# Arduino_Shield.net
KiCad netlist of a schematic drawn in Altium Designer
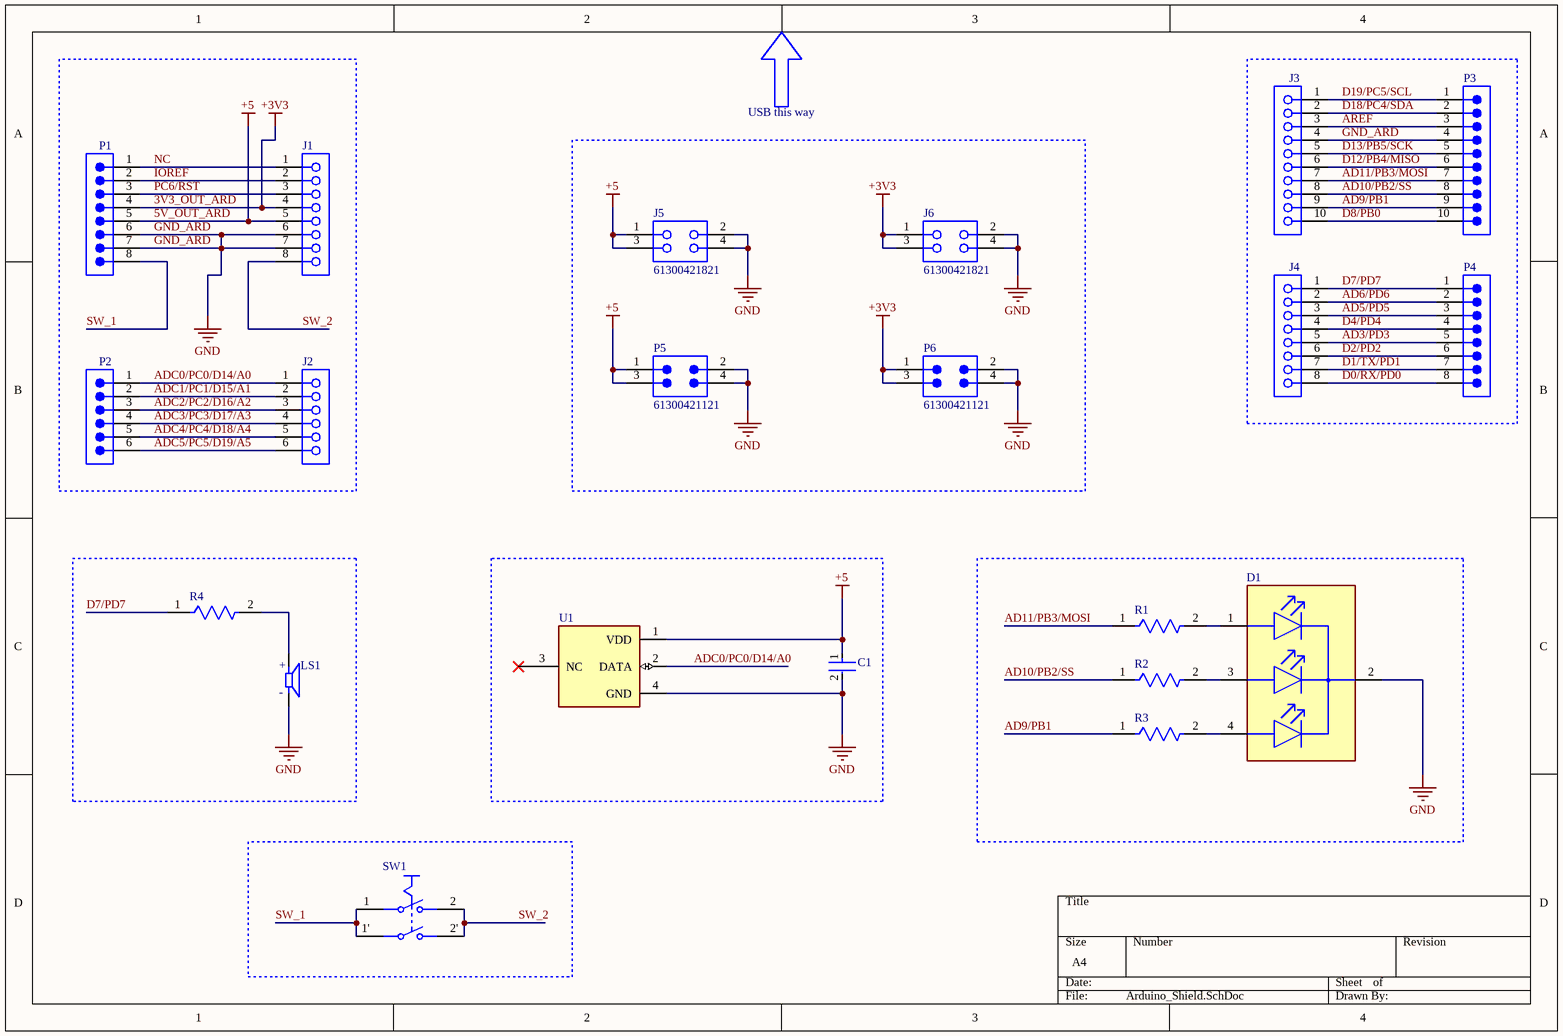
[diagram p0: Arduino_Shield.SchDoc]

(export (version "E")
  (design (tool "Eeschema 10.0.6"))
  (components
    (comp (ref "C1")
      (value "C0402C104K4RACAUTO")
      (footprint "FP-C0402-BB-MFG")
      (description "CAP CER 0.1UF 16V X7R 0402")
      (fields
        (field (name "TOLERANCE") "0.1")
        (field (name "OCTOPART") "https://octopart.com/c0402c104k4racauto-kemet-17309149")
      )
      (libsource (lib "Altium Content Vault") (part "b4654b650e69147ec39a6b967a45e02"))
    )
    (comp (ref "D1")
      (value "AAA3528LSEKJ3ZGKQBKS")
      (footprint "FP-AAA3528LSEKJ3ZGKQBKS-MFG")
      (description "LED RGB CLEAR 4SMD")
      (libsource (lib "Altium Content Vault") (part "443e5383a7a0c9f1439af3e1184479d"))
    )
    (comp (ref "J1")
      (value "61300811821")
      (footprint "61300811821")
      (description "Btb Conn, Rcpt, 8Pos, 1Row, 2.54Mm Rohs Compliant: Yes")
      (libsource (lib "Altium Content Vault") (part "Header_Female_1R_08P"))
    )
    (comp (ref "J2")
      (value "61300611821")
      (footprint "61300611821")
      (description "THT Vertical Socket Header WR-PHD, Pitch 2.54 mm, Single Row, 6 pins")
      (libsource (lib "Altium Content Vault") (part "Header_Female_1R_06P"))
    )
    (comp (ref "J3")
      (value "61301011821")
      (footprint "61301011821")
      (description "THT Vertical Socket Header WR-PHD, Pitch 2.54 mm, Single Row, 10 pins")
      (libsource (lib "Altium Content Vault") (part "Header_Female_1R_10P"))
    )
    (comp (ref "J4")
      (value "61300811821")
      (footprint "61300811821")
      (description "Btb Conn, Rcpt, 8Pos, 1Row, 2.54Mm Rohs Compliant: Yes")
      (libsource (lib "Altium Content Vault") (part "Header_Female_1R_08P"))
    )
    (comp (ref "J5")
      (value "61300421821")
      (footprint "61300421821")
      (description "THT Vertical Socket Header WR-PHD, Pitch 2.54 mm, Dual Row, 4 pins")
      (libsource (lib "Altium Content Vault") (part "Header_Female_2R_04P"))
    )
    (comp (ref "J6")
      (value "61300421821")
      (footprint "61300421821")
      (description "THT Vertical Socket Header WR-PHD, Pitch 2.54 mm, Dual Row, 4 pins")
      (libsource (lib "Altium Content Vault") (part "Header_Female_2R_04P"))
    )
    (comp (ref "LS1")
      (value "CST-951AP")
      (footprint "CUI_CST-951AP")
      (description "9 mm, 5 V, 85 dB, Through Hole, Magnetic Audio Transducer Buzzer")
      (fields (field (name "MF") "Same Sky"))
      (libsource (lib "CST-951AP") (part "CST-951AP"))
    )
    (comp (ref "P1")
      (value "61300811121")
      (footprint "61300811121")
      (description "THT Vertical Pin Header WR-PHD, Pitch 2.54 mm, Single Row, 8 pins")
      (libsource (lib "Altium Content Vault") (part "Header_Male_1R_08P"))
    )
    (comp (ref "P2")
      (value "61300611121")
      (footprint "61300611121")
      (description "THT Vertical Pin Header WR-PHD, Pitch 2.54 mm, Single Row, 6 pins")
      (libsource (lib "Altium Content Vault") (part "Header_Male_1R_06P"))
    )
    (comp (ref "P3")
      (value "61301011121")
      (footprint "61301011121")
      (description "THT Vertical Pin Header WR-PHD, Pitch 2.54 mm, Single Row, 10 pins")
      (libsource (lib "Altium Content Vault") (part "Header_Male_1R_10P"))
    )
    (comp (ref "P4")
      (value "61300811121")
      (footprint "61300811121")
      (description "THT Vertical Pin Header WR-PHD, Pitch 2.54 mm, Single Row, 8 pins")
      (libsource (lib "Altium Content Vault") (part "Header_Male_1R_08P"))
    )
    (comp (ref "P5")
      (value "61300421121")
      (footprint "61300421121")
      (description "THT Vertical Pin Header WR-PHD, Pitch 2.54 mm, Dual Row, 4 pins")
      (libsource (lib "Altium Content Vault") (part "Header_Male_2R_04P"))
    )
    (comp (ref "P6")
      (value "61300421121")
      (footprint "61300421121")
      (description "THT Vertical Pin Header WR-PHD, Pitch 2.54 mm, Dual Row, 4 pins")
      (libsource (lib "Altium Content Vault") (part "Header_Male_2R_04P"))
    )
    (comp (ref "R1")
      (value "CPF0603F1K0C1")
      (footprint "FP-CPF0603-MFG")
      (description "RES SMD 1.0KΩ 1% 1/16W 0603")
      (fields
        (field (name "OCTOPART") "https://octopart.com/cpf0603f1k0c1-te+connectivity-42013134")
        (field (name "TOLERANCE") "1%")
      )
      (libsource (lib "Altium Content Vault") (part "1029c3af85768c4190bb7ad29bc67b5"))
    )
    (comp (ref "R2")
      (value "CPF0603F1K0C1")
      (footprint "FP-CPF0603-MFG")
      (description "RES SMD 1.0KΩ 1% 1/16W 0603")
      (fields
        (field (name "OCTOPART") "https://octopart.com/cpf0603f1k0c1-te+connectivity-42013134")
        (field (name "TOLERANCE") "1%")
      )
      (libsource (lib "Altium Content Vault") (part "1029c3af85768c4190bb7ad29bc67b5"))
    )
    (comp (ref "R3")
      (value "CPF0603F1K0C1")
      (footprint "FP-CPF0603-MFG")
      (description "RES SMD 1.0KΩ 1% 1/16W 0603")
      (fields
        (field (name "OCTOPART") "https://octopart.com/cpf0603f1k0c1-te+connectivity-42013134")
        (field (name "TOLERANCE") "1%")
      )
      (libsource (lib "Altium Content Vault") (part "1029c3af85768c4190bb7ad29bc67b5"))
    )
    (comp (ref "R4")
      (value "CPF0603F1K0C1")
      (footprint "FP-CPF0603-MFG")
      (description "RES SMD 1.0KΩ 1% 1/16W 0603")
      (fields
        (field (name "OCTOPART") "https://octopart.com/cpf0603f1k0c1-te+connectivity-42013134")
        (field (name "TOLERANCE") "1%")
      )
      (libsource (lib "Altium Content Vault") (part "1029c3af85768c4190bb7ad29bc67b5"))
    )
    (comp (ref "SW1")
      (value "PVA1EEH11.2NV2")
      (footprint "FP-PVA1EEH11_2NV2-MFG")
      (description "SWITCH PUSH DPST 0.1A 32V")
      (libsource (lib "Altium Content Vault") (part "0a7b0f685d7af6e0316c3509192f32d"))
    )
    (comp (ref "U1")
      (value "ADA386")
      (footprint "XDCR_ADA386")
      (description "DHT11 basic temperature-humidity sensor + extras")
      (fields (field (name "MF") "Adafruit Industries"))
      (libsource (lib "ADA386") (part "ADA386"))
    )
  )
  (nets
    (net (code "1") (name "+3V3") (class "Default")
      (node (ref "J1") (pin "4") (pinfunction "4_4") (pintype "passive"))
      (node (ref "J6") (pin "1") (pinfunction "1_1") (pintype "passive"))
      (node (ref "J6") (pin "3") (pinfunction "3_3") (pintype "passive"))
      (node (ref "P1") (pin "4") (pinfunction "4_4") (pintype "passive"))
      (node (ref "P6") (pin "1") (pinfunction "1_1") (pintype "passive"))
      (node (ref "P6") (pin "3") (pinfunction "3_3") (pintype "passive"))
    )
    (net (code "2") (name "+5") (class "Default")
      (node (ref "C1") (pin "1") (pinfunction "1_1") (pintype "passive"))
      (node (ref "J1") (pin "5") (pinfunction "5_5") (pintype "passive"))
      (node (ref "J5") (pin "1") (pinfunction "1_1") (pintype "passive"))
      (node (ref "J5") (pin "3") (pinfunction "3_3") (pintype "passive"))
      (node (ref "P1") (pin "5") (pinfunction "5_5") (pintype "passive"))
      (node (ref "P5") (pin "1") (pinfunction "1_1") (pintype "passive"))
      (node (ref "P5") (pin "3") (pinfunction "3_3") (pintype "passive"))
      (node (ref "U1") (pin "1") (pinfunction "VDD_1") (pintype "power_in"))
    )
    (net (code "3") (name "/AD3{slash}PD3") (class "Default")
      (node (ref "J4") (pin "5") (pinfunction "5_5") (pintype "passive"))
      (node (ref "P4") (pin "5") (pinfunction "5_5") (pintype "passive"))
    )
    (net (code "4") (name "/AD5{slash}PD5") (class "Default")
      (node (ref "J4") (pin "3") (pinfunction "3_3") (pintype "passive"))
      (node (ref "P4") (pin "3") (pinfunction "3_3") (pintype "passive"))
    )
    (net (code "5") (name "/AD6{slash}PD6") (class "Default")
      (node (ref "J4") (pin "2") (pinfunction "2_2") (pintype "passive"))
      (node (ref "P4") (pin "2") (pinfunction "2_2") (pintype "passive"))
    )
    (net (code "6") (name "/AD9{slash}PB1") (class "Default")
      (node (ref "J3") (pin "9") (pinfunction "9_9") (pintype "passive"))
      (node (ref "P3") (pin "9") (pinfunction "9_9") (pintype "passive"))
      (node (ref "R3") (pin "1") (pinfunction "1_1") (pintype "passive"))
    )
    (net (code "7") (name "/AD10{slash}PB2{slash}SS") (class "Default")
      (node (ref "J3") (pin "8") (pinfunction "8_8") (pintype "passive"))
      (node (ref "P3") (pin "8") (pinfunction "8_8") (pintype "passive"))
      (node (ref "R2") (pin "1") (pinfunction "1_1") (pintype "passive"))
    )
    (net (code "8") (name "/AD11{slash}PB3{slash}MOSI") (class "Default")
      (node (ref "J3") (pin "7") (pinfunction "7_7") (pintype "passive"))
      (node (ref "P3") (pin "7") (pinfunction "7_7") (pintype "passive"))
      (node (ref "R1") (pin "1") (pinfunction "1_1") (pintype "passive"))
    )
    (net (code "9") (name "/ADC0{slash}PC0{slash}D14{slash}A0") (class "Default")
      (node (ref "J2") (pin "1") (pinfunction "1_1") (pintype "passive"))
      (node (ref "P2") (pin "1") (pinfunction "1_1") (pintype "passive"))
      (node (ref "U1") (pin "2") (pinfunction "DATA_2") (pintype "bidirectional"))
    )
    (net (code "10") (name "/ADC1{slash}PC1{slash}D15{slash}A1") (class "Default")
      (node (ref "J2") (pin "2") (pinfunction "2_2") (pintype "passive"))
      (node (ref "P2") (pin "2") (pinfunction "2_2") (pintype "passive"))
    )
    (net (code "11") (name "/ADC2{slash}PC2{slash}D16{slash}A2") (class "Default")
      (node (ref "J2") (pin "3") (pinfunction "3_3") (pintype "passive"))
      (node (ref "P2") (pin "3") (pinfunction "3_3") (pintype "passive"))
    )
    (net (code "12") (name "/ADC3{slash}PC3{slash}D17{slash}A3") (class "Default")
      (node (ref "J2") (pin "4") (pinfunction "4_4") (pintype "passive"))
      (node (ref "P2") (pin "4") (pinfunction "4_4") (pintype "passive"))
    )
    (net (code "13") (name "/ADC4{slash}PC4{slash}D18{slash}A4") (class "Default")
      (node (ref "J2") (pin "5") (pinfunction "5_5") (pintype "passive"))
      (node (ref "P2") (pin "5") (pinfunction "5_5") (pintype "passive"))
    )
    (net (code "14") (name "/ADC5{slash}PC5{slash}D19{slash}A5") (class "Default")
      (node (ref "J2") (pin "6") (pinfunction "6_6") (pintype "passive"))
      (node (ref "P2") (pin "6") (pinfunction "6_6") (pintype "passive"))
    )
    (net (code "15") (name "/AREF") (class "Default")
      (node (ref "J3") (pin "3") (pinfunction "3_3") (pintype "passive"))
      (node (ref "P3") (pin "3") (pinfunction "3_3") (pintype "passive"))
    )
    (net (code "16") (name "/D0{slash}RX{slash}PD0") (class "Default")
      (node (ref "J4") (pin "8") (pinfunction "8_8") (pintype "passive"))
      (node (ref "P4") (pin "8") (pinfunction "8_8") (pintype "passive"))
    )
    (net (code "17") (name "/D1{slash}TX{slash}PD1") (class "Default")
      (node (ref "J4") (pin "7") (pinfunction "7_7") (pintype "passive"))
      (node (ref "P4") (pin "7") (pinfunction "7_7") (pintype "passive"))
    )
    (net (code "18") (name "/D2{slash}PD2") (class "Default")
      (node (ref "J4") (pin "6") (pinfunction "6_6") (pintype "passive"))
      (node (ref "P4") (pin "6") (pinfunction "6_6") (pintype "passive"))
    )
    (net (code "19") (name "/D4{slash}PD4") (class "Default")
      (node (ref "J4") (pin "4") (pinfunction "4_4") (pintype "passive"))
      (node (ref "P4") (pin "4") (pinfunction "4_4") (pintype "passive"))
    )
    (net (code "20") (name "/D7{slash}PD7") (class "Default")
      (node (ref "J4") (pin "1") (pinfunction "1_1") (pintype "passive"))
      (node (ref "P4") (pin "1") (pinfunction "1_1") (pintype "passive"))
      (node (ref "R4") (pin "1") (pinfunction "1_1") (pintype "passive"))
    )
    (net (code "21") (name "/D8{slash}PB0") (class "Default")
      (node (ref "J3") (pin "10") (pinfunction "10_10") (pintype "passive"))
      (node (ref "P3") (pin "10") (pinfunction "10_10") (pintype "passive"))
    )
    (net (code "22") (name "/D12{slash}PB4{slash}MISO") (class "Default")
      (node (ref "J3") (pin "6") (pinfunction "6_6") (pintype "passive"))
      (node (ref "P3") (pin "6") (pinfunction "6_6") (pintype "passive"))
    )
    (net (code "23") (name "/D13{slash}PB5{slash}SCK") (class "Default")
      (node (ref "J3") (pin "5") (pinfunction "5_5") (pintype "passive"))
      (node (ref "P3") (pin "5") (pinfunction "5_5") (pintype "passive"))
    )
    (net (code "24") (name "/D18{slash}PC4{slash}SDA") (class "Default")
      (node (ref "J3") (pin "2") (pinfunction "2_2") (pintype "passive"))
      (node (ref "P3") (pin "2") (pinfunction "2_2") (pintype "passive"))
    )
    (net (code "25") (name "/D19{slash}PC5{slash}SCL") (class "Default")
      (node (ref "J3") (pin "1") (pinfunction "1_1") (pintype "passive"))
      (node (ref "P3") (pin "1") (pinfunction "1_1") (pintype "passive"))
    )
    (net (code "26") (name "/IOREF") (class "Default")
      (node (ref "J1") (pin "2") (pinfunction "2_2") (pintype "passive"))
      (node (ref "P1") (pin "2") (pinfunction "2_2") (pintype "passive"))
    )
    (net (code "27") (name "/NC") (class "Default")
      (node (ref "J1") (pin "1") (pinfunction "1_1") (pintype "passive"))
      (node (ref "P1") (pin "1") (pinfunction "1_1") (pintype "passive"))
    )
    (net (code "28") (name "/PC6{slash}RST") (class "Default")
      (node (ref "J1") (pin "3") (pinfunction "3_3") (pintype "passive"))
      (node (ref "P1") (pin "3") (pinfunction "3_3") (pintype "passive"))
    )
    (net (code "29") (name "/SW_1") (class "Default")
      (node (ref "P1") (pin "8") (pinfunction "8_8") (pintype "passive"))
      (node (ref "SW1") (pin "1") (pinfunction "1_1") (pintype "passive"))
      (node (ref "SW1") (pin "1'") (pinfunction "1'_1'") (pintype "passive"))
    )
    (net (code "30") (name "/SW_2") (class "Default")
      (node (ref "J1") (pin "8") (pinfunction "8_8") (pintype "passive"))
      (node (ref "SW1") (pin "2") (pinfunction "2_2") (pintype "passive"))
      (node (ref "SW1") (pin "2'") (pinfunction "2'_2'") (pintype "passive"))
    )
    (net (code "31") (name "GND") (class "Default")
      (node (ref "C1") (pin "2") (pinfunction "2_2") (pintype "passive"))
      (node (ref "D1") (pin "2") (pinfunction "COMMON_CATHODE_2") (pintype "passive"))
      (node (ref "J1") (pin "6") (pinfunction "6_6") (pintype "passive"))
      (node (ref "J1") (pin "7") (pinfunction "7_7") (pintype "passive"))
      (node (ref "J3") (pin "4") (pinfunction "4_4") (pintype "passive"))
      (node (ref "J5") (pin "2") (pinfunction "2_2") (pintype "passive"))
      (node (ref "J5") (pin "4") (pinfunction "4_4") (pintype "passive"))
      (node (ref "J6") (pin "2") (pinfunction "2_2") (pintype "passive"))
      (node (ref "J6") (pin "4") (pinfunction "4_4") (pintype "passive"))
      (node (ref "LS1") (pin "M") (pinfunction "M_M") (pintype "passive"))
      (node (ref "P1") (pin "6") (pinfunction "6_6") (pintype "passive"))
      (node (ref "P1") (pin "7") (pinfunction "7_7") (pintype "passive"))
      (node (ref "P3") (pin "4") (pinfunction "4_4") (pintype "passive"))
      (node (ref "P5") (pin "2") (pinfunction "2_2") (pintype "passive"))
      (node (ref "P5") (pin "4") (pinfunction "4_4") (pintype "passive"))
      (node (ref "P6") (pin "2") (pinfunction "2_2") (pintype "passive"))
      (node (ref "P6") (pin "4") (pinfunction "4_4") (pintype "passive"))
      (node (ref "U1") (pin "4") (pinfunction "GND_4") (pintype "power_in"))
    )
    (net (code "32") (name "Net-(D1-ANODE_BLUE)") (class "Default")
      (node (ref "D1") (pin "4") (pinfunction "ANODE_BLUE_4") (pintype "passive"))
      (node (ref "R3") (pin "2") (pinfunction "2_2") (pintype "passive"))
    )
    (net (code "33") (name "Net-(D1-ANODE_GREEN)") (class "Default")
      (node (ref "D1") (pin "3") (pinfunction "ANODE_GREEN_3") (pintype "passive"))
      (node (ref "R2") (pin "2") (pinfunction "2_2") (pintype "passive"))
    )
    (net (code "34") (name "Net-(D1-ANODE_RED)") (class "Default")
      (node (ref "D1") (pin "1") (pinfunction "ANODE_RED_1") (pintype "passive"))
      (node (ref "R1") (pin "2") (pinfunction "2_2") (pintype "passive"))
    )
    (net (code "35") (name "Net-(LS1-PadP)") (class "Default")
      (node (ref "LS1") (pin "P") (pinfunction "P_P") (pintype "passive"))
      (node (ref "R4") (pin "2") (pinfunction "2_2") (pintype "passive"))
    )
    (net (code "36") (name "unconnected-(U1-NC-Pad3)") (class "Default")
      (node (ref "U1") (pin "3") (pinfunction "NC_3") (pintype "passive+no_connect"))
    )
  )
)
